# belamini_breakout_v01.net
KiCad netlist of a schematic drawn in EAGLE
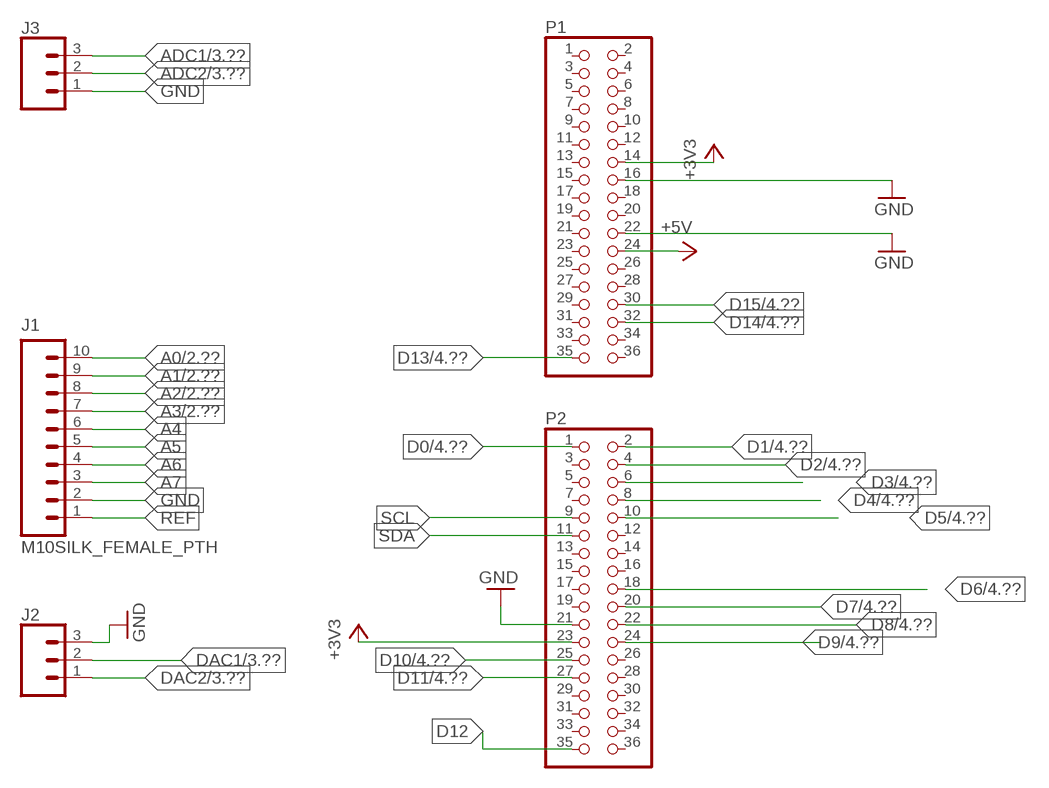
[diagram p0: schematic, sheet 1]
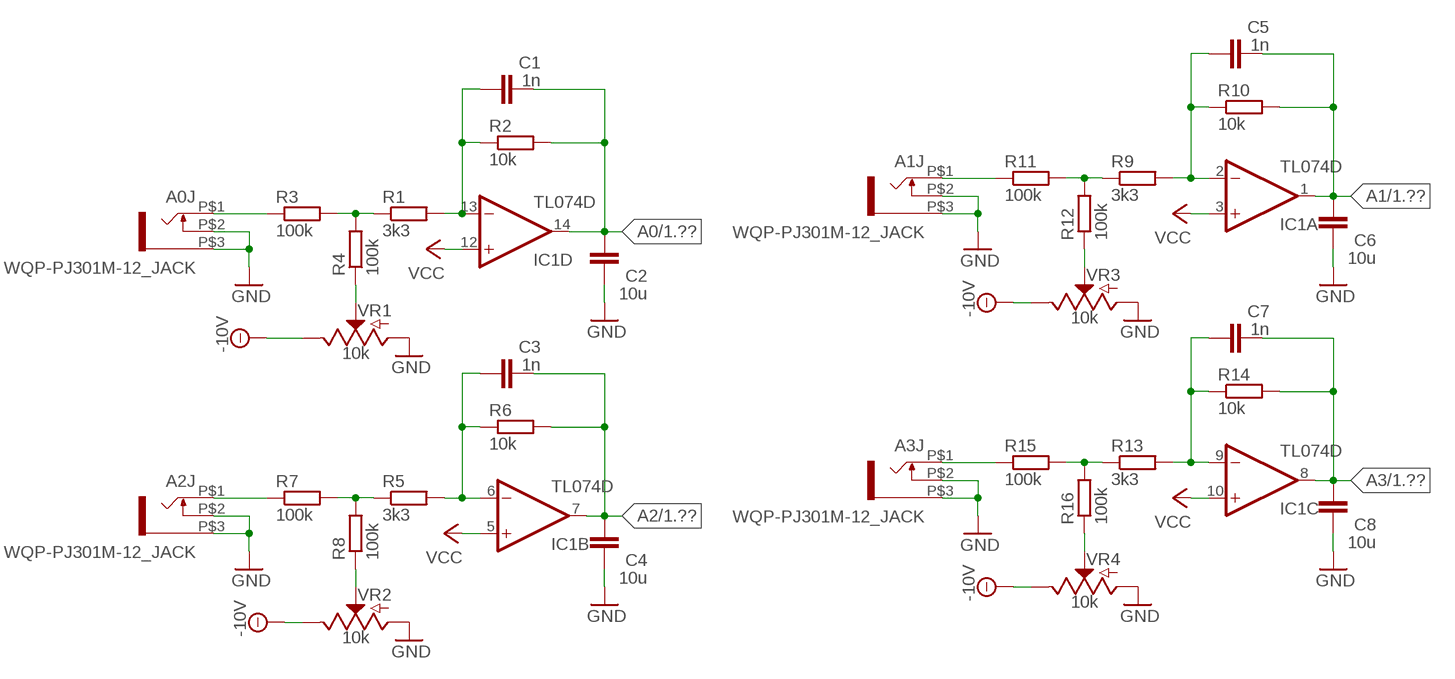
[diagram p1: schematic, sheet 2]
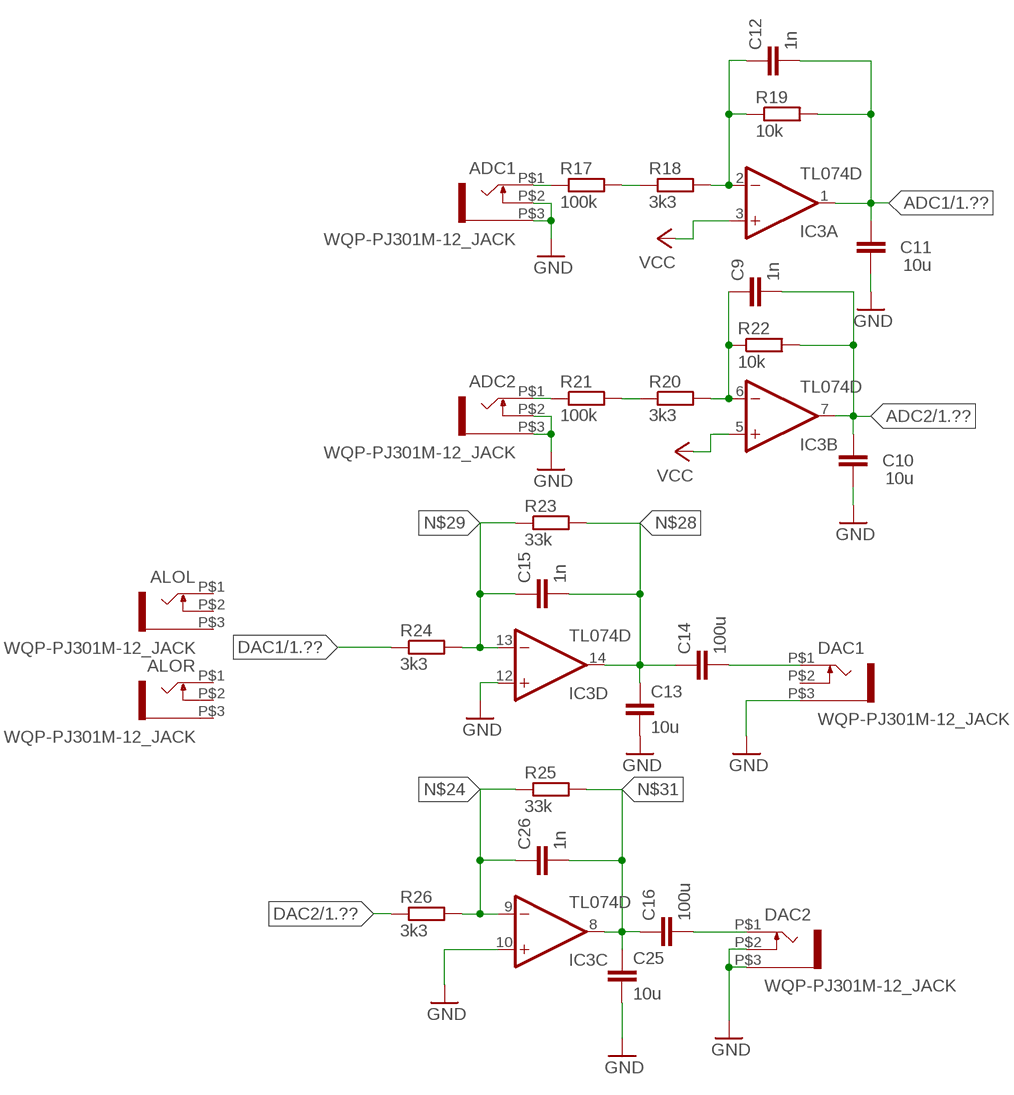
[diagram p2: schematic, sheet 3]
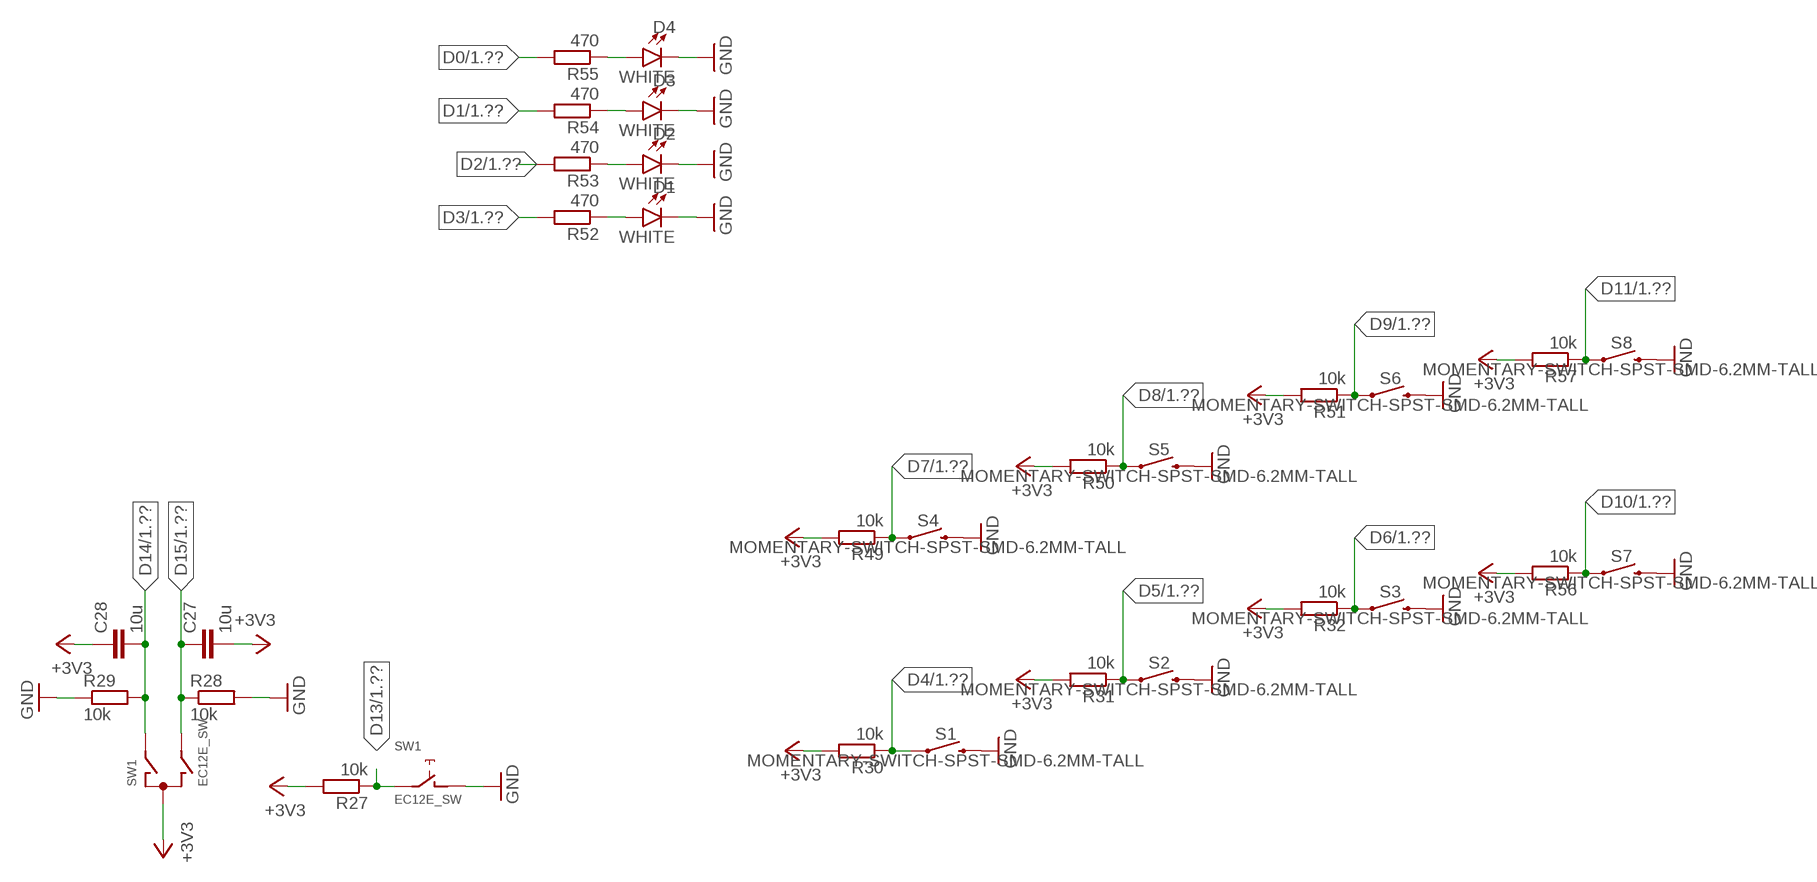
[diagram p3: schematic, sheet 4]
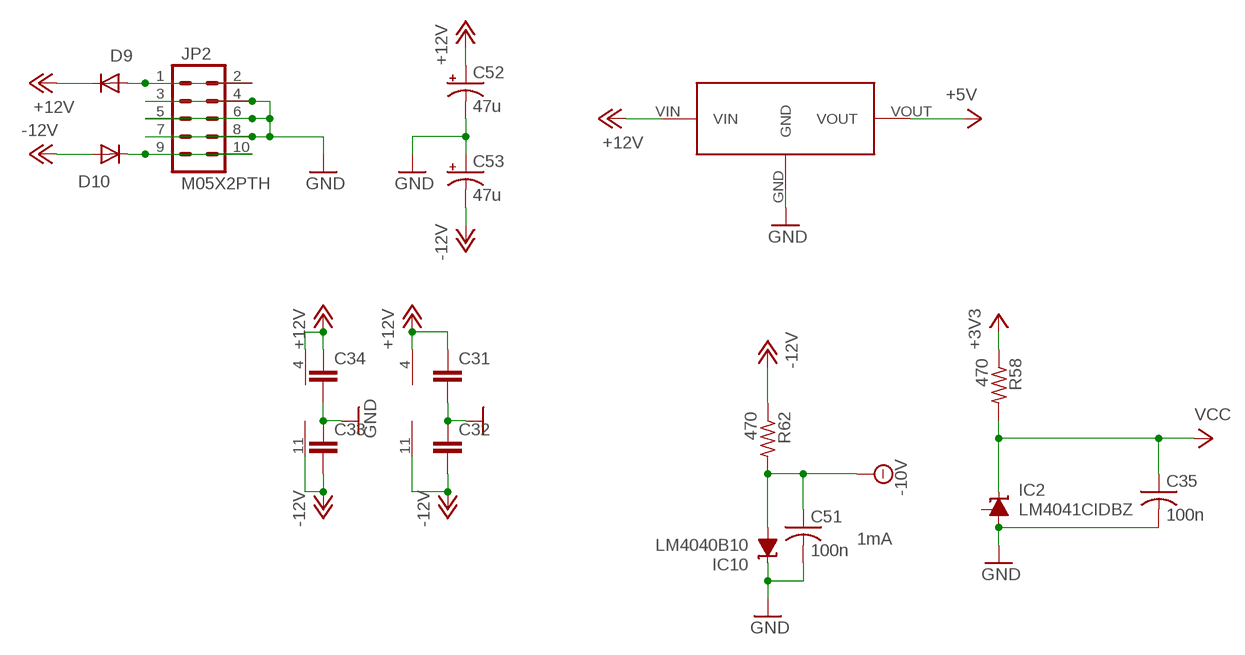
[diagram p4: schematic, sheet 5]

(export (version "E")
  (design (tool "Eeschema 10.0.6"))
  (components
    (comp (ref "C27")
      (value "10u")
      (footprint "eagle-import:C0603")
      (libsource (lib "eagle-import") (part "C-EUC0603"))
    )
    (comp (ref "C28")
      (value "10u")
      (footprint "eagle-import:C0603")
      (libsource (lib "eagle-import") (part "C-EUC0603"))
    )
    (comp (ref "D1")
      (value "WHITE")
      (footprint "eagle-import:LED-1206")
      (libsource (lib "eagle-import") (part "LED-WHITE1206"))
    )
    (comp (ref "D2")
      (value "WHITE")
      (footprint "eagle-import:LED-1206")
      (libsource (lib "eagle-import") (part "LED-WHITE1206"))
    )
    (comp (ref "D3")
      (value "WHITE")
      (footprint "eagle-import:LED-1206")
      (libsource (lib "eagle-import") (part "LED-WHITE1206"))
    )
    (comp (ref "D4")
      (value "WHITE")
      (footprint "eagle-import:LED-1206")
      (libsource (lib "eagle-import") (part "LED-WHITE1206"))
    )
    (comp (ref "R27")
      (value "10k")
      (footprint "eagle-import:R0603")
      (libsource (lib "eagle-import") (part "R-EU_R0603"))
    )
    (comp (ref "R28")
      (value "10k")
      (footprint "eagle-import:R0603")
      (libsource (lib "eagle-import") (part "R-EU_R0603"))
    )
    (comp (ref "R29")
      (value "10k")
      (footprint "eagle-import:R0603")
      (libsource (lib "eagle-import") (part "R-EU_R0603"))
    )
    (comp (ref "R30")
      (value "10k")
      (footprint "eagle-import:R0603")
      (libsource (lib "eagle-import") (part "R-EU_R0603"))
    )
    (comp (ref "R31")
      (value "10k")
      (footprint "eagle-import:R0603")
      (libsource (lib "eagle-import") (part "R-EU_R0603"))
    )
    (comp (ref "R32")
      (value "10k")
      (footprint "eagle-import:R0603")
      (libsource (lib "eagle-import") (part "R-EU_R0603"))
    )
    (comp (ref "R49")
      (value "10k")
      (footprint "eagle-import:R0603")
      (libsource (lib "eagle-import") (part "R-EU_R0603"))
    )
    (comp (ref "R50")
      (value "10k")
      (footprint "eagle-import:R0603")
      (libsource (lib "eagle-import") (part "R-EU_R0603"))
    )
    (comp (ref "R51")
      (value "10k")
      (footprint "eagle-import:R0603")
      (libsource (lib "eagle-import") (part "R-EU_R0603"))
    )
    (comp (ref "R52")
      (value "470")
      (footprint "eagle-import:R0603")
      (libsource (lib "eagle-import") (part "R-EU_R0603"))
    )
    (comp (ref "R53")
      (value "470")
      (footprint "eagle-import:R0603")
      (libsource (lib "eagle-import") (part "R-EU_R0603"))
    )
    (comp (ref "R54")
      (value "470")
      (footprint "eagle-import:R0603")
      (libsource (lib "eagle-import") (part "R-EU_R0603"))
    )
    (comp (ref "R55")
      (value "470")
      (footprint "eagle-import:R0603")
      (libsource (lib "eagle-import") (part "R-EU_R0603"))
    )
    (comp (ref "R56")
      (value "10k")
      (footprint "eagle-import:R0603")
      (libsource (lib "eagle-import") (part "R-EU_R0603"))
    )
    (comp (ref "R57")
      (value "10k")
      (footprint "eagle-import:R0603")
      (libsource (lib "eagle-import") (part "R-EU_R0603"))
    )
    (comp (ref "S1")
      (value "MOMENTARY-SWITCH-SPST-SMD-6.2MM-TALL")
      (footprint "eagle-import:TACTILE_SWITCH_SMD_6.2MM_TALL")
      (libsource (lib "eagle-import") (part "MOMENTARY-SWITCH-SPST-SMD-6.2MM-TALL"))
    )
    (comp (ref "S2")
      (value "MOMENTARY-SWITCH-SPST-SMD-6.2MM-TALL")
      (footprint "eagle-import:TACTILE_SWITCH_SMD_6.2MM_TALL")
      (libsource (lib "eagle-import") (part "MOMENTARY-SWITCH-SPST-SMD-6.2MM-TALL"))
    )
    (comp (ref "S3")
      (value "MOMENTARY-SWITCH-SPST-SMD-6.2MM-TALL")
      (footprint "eagle-import:TACTILE_SWITCH_SMD_6.2MM_TALL")
      (libsource (lib "eagle-import") (part "MOMENTARY-SWITCH-SPST-SMD-6.2MM-TALL"))
    )
    (comp (ref "S4")
      (value "MOMENTARY-SWITCH-SPST-SMD-6.2MM-TALL")
      (footprint "eagle-import:TACTILE_SWITCH_SMD_6.2MM_TALL")
      (libsource (lib "eagle-import") (part "MOMENTARY-SWITCH-SPST-SMD-6.2MM-TALL"))
    )
    (comp (ref "S5")
      (value "MOMENTARY-SWITCH-SPST-SMD-6.2MM-TALL")
      (footprint "eagle-import:TACTILE_SWITCH_SMD_6.2MM_TALL")
      (libsource (lib "eagle-import") (part "MOMENTARY-SWITCH-SPST-SMD-6.2MM-TALL"))
    )
    (comp (ref "S6")
      (value "MOMENTARY-SWITCH-SPST-SMD-6.2MM-TALL")
      (footprint "eagle-import:TACTILE_SWITCH_SMD_6.2MM_TALL")
      (libsource (lib "eagle-import") (part "MOMENTARY-SWITCH-SPST-SMD-6.2MM-TALL"))
    )
    (comp (ref "S7")
      (value "MOMENTARY-SWITCH-SPST-SMD-6.2MM-TALL")
      (footprint "eagle-import:TACTILE_SWITCH_SMD_6.2MM_TALL")
      (libsource (lib "eagle-import") (part "MOMENTARY-SWITCH-SPST-SMD-6.2MM-TALL"))
    )
    (comp (ref "S8")
      (value "MOMENTARY-SWITCH-SPST-SMD-6.2MM-TALL")
      (footprint "eagle-import:TACTILE_SWITCH_SMD_6.2MM_TALL")
      (libsource (lib "eagle-import") (part "MOMENTARY-SWITCH-SPST-SMD-6.2MM-TALL"))
    )
    (comp (ref "SW1")
      (value "EC12E_SW")
      (footprint "eagle-import:ALPS_EC12E_SW")
      (fields (field (name "MPN") "EC12E2424407"))
      (libsource (lib "eagle-import") (part "EC12E_SW"))
    )
    (comp (ref "J1")
      (value "M10SILK_FEMALE_PTH")
      (footprint "eagle-import:1X10")
      (libsource (lib "eagle-import") (part "M10SILK_FEMALE_PTH"))
    )
    (comp (ref "J2")
      (value "CONN_03")
      (footprint "eagle-import:1X03")
      (libsource (lib "eagle-import") (part "CONN_03"))
    )
    (comp (ref "J3")
      (value "CONN_03")
      (footprint "eagle-import:1X03")
      (libsource (lib "eagle-import") (part "CONN_03"))
    )
    (comp (ref "P1")
      (value "PINHD-2X18")
      (footprint "eagle-import:2X18")
      (libsource (lib "eagle-import") (part "PINHD-2X18"))
    )
    (comp (ref "P2")
      (value "PINHD-2X18")
      (footprint "eagle-import:2X18")
      (libsource (lib "eagle-import") (part "PINHD-2X18"))
    )
    (comp (ref "C31")
      (value "C-EUC0603")
      (footprint "eagle-import:C0603")
      (libsource (lib "eagle-import") (part "C-EUC0603"))
    )
    (comp (ref "C32")
      (value "C-EUC0603")
      (footprint "eagle-import:C0603")
      (libsource (lib "eagle-import") (part "C-EUC0603"))
    )
    (comp (ref "C33")
      (value "C-EUC0603")
      (footprint "eagle-import:C0603")
      (libsource (lib "eagle-import") (part "C-EUC0603"))
    )
    (comp (ref "C34")
      (value "C-EUC0603")
      (footprint "eagle-import:C0603")
      (libsource (lib "eagle-import") (part "C-EUC0603"))
    )
    (comp (ref "C35")
      (value "100n")
      (footprint "eagle-import:C0603")
      (libsource (lib "eagle-import") (part "C-USC0603"))
    )
    (comp (ref "C51")
      (value "100n")
      (footprint "eagle-import:C0603")
      (libsource (lib "eagle-import") (part "C-USC0603"))
    )
    (comp (ref "C52")
      (value "47u")
      (footprint "eagle-import:PANASONIC_D")
      (libsource (lib "eagle-import") (part "CPOL-USD"))
    )
    (comp (ref "C53")
      (value "47u")
      (footprint "eagle-import:PANASONIC_D")
      (libsource (lib "eagle-import") (part "CPOL-USD"))
    )
    (comp (ref "D9")
      (value "1N5819HW")
      (footprint "eagle-import:SOD123")
      (libsource (lib "eagle-import") (part "DIODE-SOD123"))
    )
    (comp (ref "D10")
      (value "1N5819HW")
      (footprint "eagle-import:SOD123")
      (libsource (lib "eagle-import") (part "DIODE-SOD123"))
    )
    (comp (ref "IC1")
      (value "TL074D")
      (footprint "eagle-import:SO14")
      (libsource (lib "eagle-import") (part "TL074D"))
    )
    (comp (ref "IC2")
      (value "LM4041CIDBZ")
      (footprint "eagle-import:DBZ_R-PDSO-G3")
      (fields (field (name "MF") "TEXAS INSTRUMENT CONNECTORS") (field (name "MPN") "LM4041CIDBZR"))
      (libsource (lib "eagle-import") (part "LM4041IDBZC"))
    )
    (comp (ref "IC3")
      (value "TL074D")
      (footprint "eagle-import:SO14")
      (libsource (lib "eagle-import") (part "TL074D"))
    )
    (comp (ref "IC10")
      (value "LM4040B10")
      (footprint "eagle-import:DBZ_R-PDSO-G3")
      (libsource (lib "eagle-import") (part "LM4041DBZB12"))
    )
    (comp (ref "JP2")
      (value "M05X2PTH")
      (footprint "eagle-import:AVR_ICSP")
      (libsource (lib "eagle-import") (part "M05X2PTH"))
    )
    (comp (ref "R58")
      (value "470")
      (footprint "eagle-import:R0603")
      (libsource (lib "eagle-import") (part "R-US_R0603"))
    )
    (comp (ref "R62")
      (value "470")
      (footprint "eagle-import:R0603")
      (libsource (lib "eagle-import") (part "R-US_R0603"))
    )
    (comp (ref "U$1")
      (value "RECOM785.0")
      (footprint "eagle-import:R-78XX-1.0")
      (libsource (lib "eagle-import") (part "RECOM785.0"))
    )
    (comp (ref "A0J")
      (value "WQP-PJ301M-12_JACK")
      (footprint "eagle-import:WQP-PJ301M-12_JACK")
      (libsource (lib "eagle-import") (part "WQP-PJ301M-12_JACK"))
    )
    (comp (ref "A1J")
      (value "WQP-PJ301M-12_JACK")
      (footprint "eagle-import:WQP-PJ301M-12_JACK")
      (libsource (lib "eagle-import") (part "WQP-PJ301M-12_JACK"))
    )
    (comp (ref "A2J")
      (value "WQP-PJ301M-12_JACK")
      (footprint "eagle-import:WQP-PJ301M-12_JACK")
      (libsource (lib "eagle-import") (part "WQP-PJ301M-12_JACK"))
    )
    (comp (ref "A3J")
      (value "WQP-PJ301M-12_JACK")
      (footprint "eagle-import:WQP-PJ301M-12_JACK")
      (libsource (lib "eagle-import") (part "WQP-PJ301M-12_JACK"))
    )
    (comp (ref "C1")
      (value "1n")
      (footprint "eagle-import:C0603")
      (libsource (lib "eagle-import") (part "C-EUC0603"))
    )
    (comp (ref "C2")
      (value "10u")
      (footprint "eagle-import:C0603")
      (libsource (lib "eagle-import") (part "C-EUC0603"))
    )
    (comp (ref "C3")
      (value "1n")
      (footprint "eagle-import:C0603")
      (libsource (lib "eagle-import") (part "C-EUC0603"))
    )
    (comp (ref "C4")
      (value "10u")
      (footprint "eagle-import:C0603")
      (libsource (lib "eagle-import") (part "C-EUC0603"))
    )
    (comp (ref "C5")
      (value "1n")
      (footprint "eagle-import:C0603")
      (libsource (lib "eagle-import") (part "C-EUC0603"))
    )
    (comp (ref "C6")
      (value "10u")
      (footprint "eagle-import:C0603")
      (libsource (lib "eagle-import") (part "C-EUC0603"))
    )
    (comp (ref "C7")
      (value "1n")
      (footprint "eagle-import:C0603")
      (libsource (lib "eagle-import") (part "C-EUC0603"))
    )
    (comp (ref "C8")
      (value "10u")
      (footprint "eagle-import:C0603")
      (libsource (lib "eagle-import") (part "C-EUC0603"))
    )
    (comp (ref "R1")
      (value "3k3")
      (footprint "eagle-import:R0603")
      (libsource (lib "eagle-import") (part "R-EU_R0603"))
    )
    (comp (ref "R2")
      (value "10k")
      (footprint "eagle-import:R0603")
      (libsource (lib "eagle-import") (part "R-EU_R0603"))
    )
    (comp (ref "R3")
      (value "100k")
      (footprint "eagle-import:R0603")
      (libsource (lib "eagle-import") (part "R-EU_R0603"))
    )
    (comp (ref "R4")
      (value "100k")
      (footprint "eagle-import:R0603")
      (libsource (lib "eagle-import") (part "R-EU_R0603"))
    )
    (comp (ref "R5")
      (value "3k3")
      (footprint "eagle-import:R0603")
      (libsource (lib "eagle-import") (part "R-EU_R0603"))
    )
    (comp (ref "R6")
      (value "10k")
      (footprint "eagle-import:R0603")
      (libsource (lib "eagle-import") (part "R-EU_R0603"))
    )
    (comp (ref "R7")
      (value "100k")
      (footprint "eagle-import:R0603")
      (libsource (lib "eagle-import") (part "R-EU_R0603"))
    )
    (comp (ref "R8")
      (value "100k")
      (footprint "eagle-import:R0603")
      (libsource (lib "eagle-import") (part "R-EU_R0603"))
    )
    (comp (ref "R9")
      (value "3k3")
      (footprint "eagle-import:R0603")
      (libsource (lib "eagle-import") (part "R-EU_R0603"))
    )
    (comp (ref "R10")
      (value "10k")
      (footprint "eagle-import:R0603")
      (libsource (lib "eagle-import") (part "R-EU_R0603"))
    )
    (comp (ref "R11")
      (value "100k")
      (footprint "eagle-import:R0603")
      (libsource (lib "eagle-import") (part "R-EU_R0603"))
    )
    (comp (ref "R12")
      (value "100k")
      (footprint "eagle-import:R0603")
      (libsource (lib "eagle-import") (part "R-EU_R0603"))
    )
    (comp (ref "R13")
      (value "3k3")
      (footprint "eagle-import:R0603")
      (libsource (lib "eagle-import") (part "R-EU_R0603"))
    )
    (comp (ref "R14")
      (value "10k")
      (footprint "eagle-import:R0603")
      (libsource (lib "eagle-import") (part "R-EU_R0603"))
    )
    (comp (ref "R15")
      (value "100k")
      (footprint "eagle-import:R0603")
      (libsource (lib "eagle-import") (part "R-EU_R0603"))
    )
    (comp (ref "R16")
      (value "100k")
      (footprint "eagle-import:R0603")
      (libsource (lib "eagle-import") (part "R-EU_R0603"))
    )
    (comp (ref "VR1")
      (value "10k")
      (footprint "eagle-import:POT-PTH-ALPS-KIT")
      (libsource (lib "eagle-import") (part "POTENTIOMETER-PTH-9MM-1/20W-20%-KIT"))
    )
    (comp (ref "VR2")
      (value "10k")
      (footprint "eagle-import:POT-PTH-ALPS-KIT")
      (libsource (lib "eagle-import") (part "POTENTIOMETER-PTH-9MM-1/20W-20%-KIT"))
    )
    (comp (ref "VR3")
      (value "10k")
      (footprint "eagle-import:POT-PTH-ALPS-KIT")
      (libsource (lib "eagle-import") (part "POTENTIOMETER-PTH-9MM-1/20W-20%-KIT"))
    )
    (comp (ref "VR4")
      (value "10k")
      (footprint "eagle-import:POT-PTH-ALPS-KIT")
      (libsource (lib "eagle-import") (part "POTENTIOMETER-PTH-9MM-1/20W-20%-KIT"))
    )
    (comp (ref "ADC1")
      (value "WQP-PJ301M-12_JACK")
      (footprint "eagle-import:WQP-PJ301M-12_JACK")
      (libsource (lib "eagle-import") (part "WQP-PJ301M-12_JACK"))
    )
    (comp (ref "ADC2")
      (value "WQP-PJ301M-12_JACK")
      (footprint "eagle-import:WQP-PJ301M-12_JACK")
      (libsource (lib "eagle-import") (part "WQP-PJ301M-12_JACK"))
    )
    (comp (ref "ALOL")
      (value "WQP-PJ301M-12_JACK")
      (footprint "eagle-import:WQP-PJ301M-12_JACK")
      (libsource (lib "eagle-import") (part "WQP-PJ301M-12_JACK"))
    )
    (comp (ref "ALOR")
      (value "WQP-PJ301M-12_JACK")
      (footprint "eagle-import:WQP-PJ301M-12_JACK")
      (libsource (lib "eagle-import") (part "WQP-PJ301M-12_JACK"))
    )
    (comp (ref "C9")
      (value "1n")
      (footprint "eagle-import:C0603")
      (libsource (lib "eagle-import") (part "C-EUC0603"))
    )
    (comp (ref "C10")
      (value "10u")
      (footprint "eagle-import:C0603")
      (libsource (lib "eagle-import") (part "C-EUC0603"))
    )
    (comp (ref "C11")
      (value "10u")
      (footprint "eagle-import:C0603")
      (libsource (lib "eagle-import") (part "C-EUC0603"))
    )
    (comp (ref "C12")
      (value "1n")
      (footprint "eagle-import:C0603")
      (libsource (lib "eagle-import") (part "C-EUC0603"))
    )
    (comp (ref "C13")
      (value "10u")
      (footprint "eagle-import:C0603")
      (libsource (lib "eagle-import") (part "C-EUC0603"))
    )
    (comp (ref "C14")
      (value "100u")
      (footprint "eagle-import:C0603")
      (libsource (lib "eagle-import") (part "C-EUC0603"))
    )
    (comp (ref "C15")
      (value "1n")
      (footprint "eagle-import:C0603")
      (libsource (lib "eagle-import") (part "C-EUC0603"))
    )
    (comp (ref "C16")
      (value "100u")
      (footprint "eagle-import:C0603")
      (libsource (lib "eagle-import") (part "C-EUC0603"))
    )
    (comp (ref "C25")
      (value "10u")
      (footprint "eagle-import:C0603")
      (libsource (lib "eagle-import") (part "C-EUC0603"))
    )
    (comp (ref "C26")
      (value "1n")
      (footprint "eagle-import:C0603")
      (libsource (lib "eagle-import") (part "C-EUC0603"))
    )
    (comp (ref "DAC1")
      (value "WQP-PJ301M-12_JACK")
      (footprint "eagle-import:WQP-PJ301M-12_JACK")
      (libsource (lib "eagle-import") (part "WQP-PJ301M-12_JACK"))
    )
    (comp (ref "DAC2")
      (value "WQP-PJ301M-12_JACK")
      (footprint "eagle-import:WQP-PJ301M-12_JACK")
      (libsource (lib "eagle-import") (part "WQP-PJ301M-12_JACK"))
    )
    (comp (ref "R17")
      (value "100k")
      (footprint "eagle-import:R0603")
      (libsource (lib "eagle-import") (part "R-EU_R0603"))
    )
    (comp (ref "R18")
      (value "3k3")
      (footprint "eagle-import:R0603")
      (libsource (lib "eagle-import") (part "R-EU_R0603"))
    )
    (comp (ref "R19")
      (value "10k")
      (footprint "eagle-import:R0603")
      (libsource (lib "eagle-import") (part "R-EU_R0603"))
    )
    (comp (ref "R20")
      (value "3k3")
      (footprint "eagle-import:R0603")
      (libsource (lib "eagle-import") (part "R-EU_R0603"))
    )
    (comp (ref "R21")
      (value "100k")
      (footprint "eagle-import:R0603")
      (libsource (lib "eagle-import") (part "R-EU_R0603"))
    )
    (comp (ref "R22")
      (value "10k")
      (footprint "eagle-import:R0603")
      (libsource (lib "eagle-import") (part "R-EU_R0603"))
    )
    (comp (ref "R23")
      (value "33k")
      (footprint "eagle-import:R0603")
      (libsource (lib "eagle-import") (part "R-EU_R0603"))
    )
    (comp (ref "R24")
      (value "3k3")
      (footprint "eagle-import:R0603")
      (libsource (lib "eagle-import") (part "R-EU_R0603"))
    )
    (comp (ref "R25")
      (value "33k")
      (footprint "eagle-import:R0603")
      (libsource (lib "eagle-import") (part "R-EU_R0603"))
    )
    (comp (ref "R26")
      (value "3k3")
      (footprint "eagle-import:R0603")
      (libsource (lib "eagle-import") (part "R-EU_R0603"))
    )
  )
  (nets
    (net (code "1") (name "+3V3") (class "Default")
      (node (ref "C27") (pin "2") (pinfunction "2_2") (pintype "passive"))
      (node (ref "C28") (pin "1") (pinfunction "1_1") (pintype "passive"))
      (node (ref "P1") (pin "14") (pinfunction "14_14") (pintype "passive"))
      (node (ref "P2") (pin "23") (pinfunction "23_23") (pintype "passive"))
      (node (ref "R27") (pin "2") (pinfunction "2_2") (pintype "passive"))
      (node (ref "R30") (pin "2") (pinfunction "2_2") (pintype "passive"))
      (node (ref "R31") (pin "2") (pinfunction "2_2") (pintype "passive"))
      (node (ref "R32") (pin "2") (pinfunction "2_2") (pintype "passive"))
      (node (ref "R49") (pin "2") (pinfunction "2_2") (pintype "passive"))
      (node (ref "R50") (pin "2") (pinfunction "2_2") (pintype "passive"))
      (node (ref "R51") (pin "2") (pinfunction "2_2") (pintype "passive"))
      (node (ref "R56") (pin "2") (pinfunction "2_2") (pintype "passive"))
      (node (ref "R57") (pin "2") (pinfunction "2_2") (pintype "passive"))
      (node (ref "R58") (pin "1") (pinfunction "1_1") (pintype "passive"))
      (node (ref "SW1") (pin "C") (pinfunction "C_C") (pintype "passive"))
    )
    (net (code "2") (name "+5V") (class "Default")
      (node (ref "P1") (pin "24") (pinfunction "24_24") (pintype "passive"))
      (node (ref "U$1") (pin "VOUT") (pinfunction "VOUT_VOUT") (pintype "bidirectional"))
    )
    (net (code "3") (name "+12V") (class "Default")
      (node (ref "C31") (pin "1") (pinfunction "1_1") (pintype "passive"))
      (node (ref "C34") (pin "1") (pinfunction "1_1") (pintype "passive"))
      (node (ref "C52") (pin "+") (pinfunction "+_+") (pintype "passive"))
      (node (ref "D9") (pin "C") (pinfunction "C_C") (pintype "passive"))
      (node (ref "IC1") (pin "4") (pinfunction "V+_4") (pintype "power_in"))
      (node (ref "IC3") (pin "4") (pinfunction "V+_4") (pintype "power_in"))
      (node (ref "U$1") (pin "VIN") (pinfunction "VIN_VIN") (pintype "bidirectional"))
    )
    (net (code "4") (name "-10V") (class "Default")
      (node (ref "C51") (pin "1") (pinfunction "1_1") (pintype "passive"))
      (node (ref "IC10") (pin "2") (pinfunction "A_2") (pintype "passive"))
      (node (ref "R62") (pin "2") (pinfunction "2_2") (pintype "passive"))
      (node (ref "VR1") (pin "P$1") (pinfunction "E_P$1") (pintype "passive"))
      (node (ref "VR2") (pin "P$1") (pinfunction "E_P$1") (pintype "passive"))
      (node (ref "VR3") (pin "P$1") (pinfunction "E_P$1") (pintype "passive"))
      (node (ref "VR4") (pin "P$1") (pinfunction "E_P$1") (pintype "passive"))
    )
    (net (code "5") (name "-12V") (class "Default")
      (node (ref "C32") (pin "2") (pinfunction "2_2") (pintype "passive"))
      (node (ref "C33") (pin "2") (pinfunction "2_2") (pintype "passive"))
      (node (ref "C53") (pin "-") (pinfunction "-_-") (pintype "passive"))
      (node (ref "D10") (pin "A") (pinfunction "A_A") (pintype "passive"))
      (node (ref "IC1") (pin "11") (pinfunction "V-_11") (pintype "power_in"))
      (node (ref "IC3") (pin "11") (pinfunction "V-_11") (pintype "power_in"))
      (node (ref "R62") (pin "1") (pinfunction "1_1") (pintype "passive"))
    )
    (net (code "6") (name "A0") (class "Default")
      (node (ref "C1") (pin "2") (pinfunction "2_2") (pintype "passive"))
      (node (ref "C2") (pin "2") (pinfunction "2_2") (pintype "passive"))
      (node (ref "IC1") (pin "14") (pinfunction "OUT_14") (pintype "output"))
      (node (ref "J1") (pin "10") (pinfunction "10_10") (pintype "passive"))
      (node (ref "R2") (pin "2") (pinfunction "2_2") (pintype "passive"))
    )
    (net (code "7") (name "A1") (class "Default")
      (node (ref "C5") (pin "2") (pinfunction "2_2") (pintype "passive"))
      (node (ref "C6") (pin "2") (pinfunction "2_2") (pintype "passive"))
      (node (ref "IC1") (pin "1") (pinfunction "OUT_1") (pintype "output"))
      (node (ref "J1") (pin "9") (pinfunction "9_9") (pintype "passive"))
      (node (ref "R10") (pin "2") (pinfunction "2_2") (pintype "passive"))
    )
    (net (code "8") (name "A2") (class "Default")
      (node (ref "C3") (pin "2") (pinfunction "2_2") (pintype "passive"))
      (node (ref "C4") (pin "2") (pinfunction "2_2") (pintype "passive"))
      (node (ref "IC1") (pin "7") (pinfunction "OUT_7") (pintype "output"))
      (node (ref "J1") (pin "8") (pinfunction "8_8") (pintype "passive"))
      (node (ref "R6") (pin "2") (pinfunction "2_2") (pintype "passive"))
    )
    (net (code "9") (name "A3") (class "Default")
      (node (ref "C7") (pin "2") (pinfunction "2_2") (pintype "passive"))
      (node (ref "C8") (pin "2") (pinfunction "2_2") (pintype "passive"))
      (node (ref "IC1") (pin "8") (pinfunction "OUT_8") (pintype "output"))
      (node (ref "J1") (pin "7") (pinfunction "7_7") (pintype "passive"))
      (node (ref "R14") (pin "2") (pinfunction "2_2") (pintype "passive"))
    )
    (net (code "10") (name "A4") (class "Default")
      (node (ref "J1") (pin "6") (pinfunction "6_6") (pintype "passive"))
    )
    (net (code "11") (name "A5") (class "Default")
      (node (ref "J1") (pin "5") (pinfunction "5_5") (pintype "passive"))
    )
    (net (code "12") (name "A6") (class "Default")
      (node (ref "J1") (pin "4") (pinfunction "4_4") (pintype "passive"))
    )
    (net (code "13") (name "A7") (class "Default")
      (node (ref "J1") (pin "3") (pinfunction "3_3") (pintype "passive"))
    )
    (net (code "14") (name "ADC1") (class "Default")
      (node (ref "C11") (pin "2") (pinfunction "2_2") (pintype "passive"))
      (node (ref "C12") (pin "2") (pinfunction "2_2") (pintype "passive"))
      (node (ref "IC3") (pin "1") (pinfunction "OUT_1") (pintype "output"))
      (node (ref "J3") (pin "3") (pinfunction "3_3") (pintype "passive"))
      (node (ref "R19") (pin "2") (pinfunction "2_2") (pintype "passive"))
    )
    (net (code "15") (name "ADC2") (class "Default")
      (node (ref "C10") (pin "2") (pinfunction "2_2") (pintype "passive"))
      (node (ref "C9") (pin "2") (pinfunction "2_2") (pintype "passive"))
      (node (ref "IC3") (pin "7") (pinfunction "OUT_7") (pintype "output"))
      (node (ref "J3") (pin "2") (pinfunction "2_2") (pintype "passive"))
      (node (ref "R22") (pin "2") (pinfunction "2_2") (pintype "passive"))
    )
    (net (code "16") (name "D0") (class "Default")
      (node (ref "P2") (pin "1") (pinfunction "1_1") (pintype "passive"))
      (node (ref "R55") (pin "2") (pinfunction "2_2") (pintype "passive"))
    )
    (net (code "17") (name "D1") (class "Default")
      (node (ref "P2") (pin "2") (pinfunction "2_2") (pintype "passive"))
      (node (ref "R54") (pin "2") (pinfunction "2_2") (pintype "passive"))
    )
    (net (code "18") (name "D2") (class "Default")
      (node (ref "P2") (pin "4") (pinfunction "4_4") (pintype "passive"))
      (node (ref "R53") (pin "2") (pinfunction "2_2") (pintype "passive"))
    )
    (net (code "19") (name "D3") (class "Default")
      (node (ref "P2") (pin "6") (pinfunction "6_6") (pintype "passive"))
      (node (ref "R52") (pin "2") (pinfunction "2_2") (pintype "passive"))
    )
    (net (code "20") (name "D4") (class "Default")
      (node (ref "P2") (pin "8") (pinfunction "8_8") (pintype "passive"))
      (node (ref "R30") (pin "1") (pinfunction "1_1") (pintype "passive"))
      (node (ref "S1") (pin "A2") (pinfunction "1_A2") (pintype "passive"))
    )
    (net (code "21") (name "D5") (class "Default")
      (node (ref "P2") (pin "10") (pinfunction "10_10") (pintype "passive"))
      (node (ref "R31") (pin "1") (pinfunction "1_1") (pintype "passive"))
      (node (ref "S2") (pin "A2") (pinfunction "1_A2") (pintype "passive"))
    )
    (net (code "22") (name "D6") (class "Default")
      (node (ref "P2") (pin "18") (pinfunction "18_18") (pintype "passive"))
      (node (ref "R32") (pin "1") (pinfunction "1_1") (pintype "passive"))
      (node (ref "S3") (pin "A2") (pinfunction "1_A2") (pintype "passive"))
    )
    (net (code "23") (name "D7") (class "Default")
      (node (ref "P2") (pin "20") (pinfunction "20_20") (pintype "passive"))
      (node (ref "R49") (pin "1") (pinfunction "1_1") (pintype "passive"))
      (node (ref "S4") (pin "A2") (pinfunction "1_A2") (pintype "passive"))
    )
    (net (code "24") (name "D8") (class "Default")
      (node (ref "P2") (pin "22") (pinfunction "22_22") (pintype "passive"))
      (node (ref "R50") (pin "1") (pinfunction "1_1") (pintype "passive"))
      (node (ref "S5") (pin "A2") (pinfunction "1_A2") (pintype "passive"))
    )
    (net (code "25") (name "D9") (class "Default")
      (node (ref "P2") (pin "24") (pinfunction "24_24") (pintype "passive"))
      (node (ref "R51") (pin "1") (pinfunction "1_1") (pintype "passive"))
      (node (ref "S6") (pin "A2") (pinfunction "1_A2") (pintype "passive"))
    )
    (net (code "26") (name "D10") (class "Default")
      (node (ref "P2") (pin "25") (pinfunction "25_25") (pintype "passive"))
      (node (ref "R56") (pin "1") (pinfunction "1_1") (pintype "passive"))
      (node (ref "S7") (pin "A2") (pinfunction "1_A2") (pintype "passive"))
    )
    (net (code "27") (name "D11") (class "Default")
      (node (ref "P2") (pin "27") (pinfunction "27_27") (pintype "passive"))
      (node (ref "R57") (pin "1") (pinfunction "1_1") (pintype "passive"))
      (node (ref "S8") (pin "A2") (pinfunction "1_A2") (pintype "passive"))
    )
    (net (code "28") (name "D12") (class "Default")
      (node (ref "P2") (pin "35") (pinfunction "35_35") (pintype "passive"))
    )
    (net (code "29") (name "D13") (class "Default")
      (node (ref "P1") (pin "35") (pinfunction "35_35") (pintype "passive"))
      (node (ref "R27") (pin "1") (pinfunction "1_1") (pintype "passive"))
      (node (ref "SW1") (pin "E") (pinfunction "2_E") (pintype "passive"))
    )
    (net (code "30") (name "D14") (class "Default")
      (node (ref "C28") (pin "2") (pinfunction "2_2") (pintype "passive"))
      (node (ref "P1") (pin "32") (pinfunction "32_32") (pintype "passive"))
      (node (ref "R29") (pin "2") (pinfunction "2_2") (pintype "passive"))
      (node (ref "SW1") (pin "A") (pinfunction "A_A") (pintype "passive"))
    )
    (net (code "31") (name "D15") (class "Default")
      (node (ref "C27") (pin "1") (pinfunction "1_1") (pintype "passive"))
      (node (ref "P1") (pin "30") (pinfunction "30_30") (pintype "passive"))
      (node (ref "R28") (pin "1") (pinfunction "1_1") (pintype "passive"))
      (node (ref "SW1") (pin "B") (pinfunction "B_B") (pintype "passive"))
    )
    (net (code "32") (name "DAC1") (class "Default")
      (node (ref "J2") (pin "2") (pinfunction "2_2") (pintype "passive"))
      (node (ref "R24") (pin "1") (pinfunction "1_1") (pintype "passive"))
    )
    (net (code "33") (name "DAC2") (class "Default")
      (node (ref "J2") (pin "1") (pinfunction "1_1") (pintype "passive"))
      (node (ref "R26") (pin "1") (pinfunction "1_1") (pintype "passive"))
    )
    (net (code "34") (name "GND") (class "Default")
      (node (ref "A0J") (pin "P$2") (pinfunction "3_P$2") (pintype "passive"))
      (node (ref "A0J") (pin "P$3") (pinfunction "1_P$3") (pintype "passive"))
      (node (ref "A1J") (pin "P$2") (pinfunction "3_P$2") (pintype "passive"))
      (node (ref "A1J") (pin "P$3") (pinfunction "1_P$3") (pintype "passive"))
      (node (ref "A2J") (pin "P$2") (pinfunction "3_P$2") (pintype "passive"))
      (node (ref "A2J") (pin "P$3") (pinfunction "1_P$3") (pintype "passive"))
      (node (ref "A3J") (pin "P$2") (pinfunction "3_P$2") (pintype "passive"))
      (node (ref "A3J") (pin "P$3") (pinfunction "1_P$3") (pintype "passive"))
      (node (ref "ADC1") (pin "P$2") (pinfunction "3_P$2") (pintype "passive"))
      (node (ref "ADC1") (pin "P$3") (pinfunction "1_P$3") (pintype "passive"))
      (node (ref "ADC2") (pin "P$2") (pinfunction "3_P$2") (pintype "passive"))
      (node (ref "ADC2") (pin "P$3") (pinfunction "1_P$3") (pintype "passive"))
      (node (ref "C10") (pin "1") (pinfunction "1_1") (pintype "passive"))
      (node (ref "C11") (pin "1") (pinfunction "1_1") (pintype "passive"))
      (node (ref "C13") (pin "2") (pinfunction "2_2") (pintype "passive"))
      (node (ref "C2") (pin "1") (pinfunction "1_1") (pintype "passive"))
      (node (ref "C25") (pin "2") (pinfunction "2_2") (pintype "passive"))
      (node (ref "C31") (pin "2") (pinfunction "2_2") (pintype "passive"))
      (node (ref "C32") (pin "1") (pinfunction "1_1") (pintype "passive"))
      (node (ref "C33") (pin "1") (pinfunction "1_1") (pintype "passive"))
      (node (ref "C34") (pin "2") (pinfunction "2_2") (pintype "passive"))
      (node (ref "C35") (pin "2") (pinfunction "2_2") (pintype "passive"))
      (node (ref "C4") (pin "1") (pinfunction "1_1") (pintype "passive"))
      (node (ref "C51") (pin "2") (pinfunction "2_2") (pintype "passive"))
      (node (ref "C52") (pin "-") (pinfunction "-_-") (pintype "passive"))
      (node (ref "C53") (pin "+") (pinfunction "+_+") (pintype "passive"))
      (node (ref "C6") (pin "1") (pinfunction "1_1") (pintype "passive"))
      (node (ref "C8") (pin "1") (pinfunction "1_1") (pintype "passive"))
      (node (ref "D1") (pin "C") (pinfunction "C_C") (pintype "passive"))
      (node (ref "D2") (pin "C") (pinfunction "C_C") (pintype "passive"))
      (node (ref "D3") (pin "C") (pinfunction "C_C") (pintype "passive"))
      (node (ref "D4") (pin "C") (pinfunction "C_C") (pintype "passive"))
      (node (ref "DAC1") (pin "P$3") (pinfunction "1_P$3") (pintype "passive"))
      (node (ref "DAC2") (pin "P$2") (pinfunction "3_P$2") (pintype "passive"))
      (node (ref "DAC2") (pin "P$3") (pinfunction "1_P$3") (pintype "passive"))
      (node (ref "IC10") (pin "1") (pinfunction "C_1") (pintype "passive"))
      (node (ref "IC2") (pin "3") (pinfunction "A_3") (pintype "passive"))
      (node (ref "IC3") (pin "10") (pinfunction "+IN_10") (pintype "input"))
      (node (ref "IC3") (pin "12") (pinfunction "+IN_12") (pintype "input"))
      (node (ref "J1") (pin "2") (pinfunction "2_2") (pintype "passive"))
      (node (ref "J2") (pin "3") (pinfunction "3_3") (pintype "passive"))
      (node (ref "J3") (pin "1") (pinfunction "1_1") (pintype "passive"))
      (node (ref "JP2") (pin "3") (pinfunction "3_3") (pintype "passive"))
      (node (ref "JP2") (pin "4") (pinfunction "4_4") (pintype "passive"))
      (node (ref "JP2") (pin "5") (pinfunction "5_5") (pintype "passive"))
      (node (ref "JP2") (pin "6") (pinfunction "6_6") (pintype "passive"))
      (node (ref "JP2") (pin "7") (pinfunction "7_7") (pintype "passive"))
      (node (ref "JP2") (pin "8") (pinfunction "8_8") (pintype "passive"))
      (node (ref "P1") (pin "16") (pinfunction "16_16") (pintype "passive"))
      (node (ref "P1") (pin "22") (pinfunction "22_22") (pintype "passive"))
      (node (ref "P2") (pin "21") (pinfunction "21_21") (pintype "passive"))
      (node (ref "R28") (pin "2") (pinfunction "2_2") (pintype "passive"))
      (node (ref "R29") (pin "1") (pinfunction "1_1") (pintype "passive"))
      (node (ref "S1") (pin "B2") (pinfunction "2_B2") (pintype "passive"))
      (node (ref "S2") (pin "B2") (pinfunction "2_B2") (pintype "passive"))
      (node (ref "S3") (pin "B2") (pinfunction "2_B2") (pintype "passive"))
      (node (ref "S4") (pin "B2") (pinfunction "2_B2") (pintype "passive"))
      (node (ref "S5") (pin "B2") (pinfunction "2_B2") (pintype "passive"))
      (node (ref "S6") (pin "B2") (pinfunction "2_B2") (pintype "passive"))
      (node (ref "S7") (pin "B2") (pinfunction "2_B2") (pintype "passive"))
      (node (ref "S8") (pin "B2") (pinfunction "2_B2") (pintype "passive"))
      (node (ref "SW1") (pin "D") (pinfunction "1_D") (pintype "passive"))
      (node (ref "U$1") (pin "GND") (pinfunction "GND_GND") (pintype "bidirectional"))
      (node (ref "VR1") (pin "P$3") (pinfunction "A_P$3") (pintype "passive"))
      (node (ref "VR2") (pin "P$3") (pinfunction "A_P$3") (pintype "passive"))
      (node (ref "VR3") (pin "P$3") (pinfunction "A_P$3") (pintype "passive"))
      (node (ref "VR4") (pin "P$3") (pinfunction "A_P$3") (pintype "passive"))
    )
    (net (code "35") (name "N$24") (class "Default")
      (node (ref "C26") (pin "1") (pinfunction "1_1") (pintype "passive"))
      (node (ref "IC3") (pin "9") (pinfunction "-IN_9") (pintype "input"))
      (node (ref "R25") (pin "1") (pinfunction "1_1") (pintype "passive"))
      (node (ref "R26") (pin "2") (pinfunction "2_2") (pintype "passive"))
    )
    (net (code "36") (name "N$28") (class "Default")
      (node (ref "C13") (pin "1") (pinfunction "1_1") (pintype "passive"))
      (node (ref "C14") (pin "1") (pinfunction "1_1") (pintype "passive"))
      (node (ref "C15") (pin "2") (pinfunction "2_2") (pintype "passive"))
      (node (ref "IC3") (pin "14") (pinfunction "OUT_14") (pintype "output"))
      (node (ref "R23") (pin "2") (pinfunction "2_2") (pintype "passive"))
    )
    (net (code "37") (name "N$29") (class "Default")
      (node (ref "C15") (pin "1") (pinfunction "1_1") (pintype "passive"))
      (node (ref "IC3") (pin "13") (pinfunction "-IN_13") (pintype "input"))
      (node (ref "R23") (pin "1") (pinfunction "1_1") (pintype "passive"))
      (node (ref "R24") (pin "2") (pinfunction "2_2") (pintype "passive"))
    )
    (net (code "38") (name "N$31") (class "Default")
      (node (ref "C16") (pin "1") (pinfunction "1_1") (pintype "passive"))
      (node (ref "C25") (pin "1") (pinfunction "1_1") (pintype "passive"))
      (node (ref "C26") (pin "2") (pinfunction "2_2") (pintype "passive"))
      (node (ref "IC3") (pin "8") (pinfunction "OUT_8") (pintype "output"))
      (node (ref "R25") (pin "2") (pinfunction "2_2") (pintype "passive"))
    )
    (net (code "39") (name "Net-(A0J-2)") (class "Default")
      (node (ref "A0J") (pin "P$1") (pinfunction "2_P$1") (pintype "passive"))
      (node (ref "R3") (pin "1") (pinfunction "1_1") (pintype "passive"))
    )
    (net (code "40") (name "Net-(A1J-2)") (class "Default")
      (node (ref "A1J") (pin "P$1") (pinfunction "2_P$1") (pintype "passive"))
      (node (ref "R11") (pin "1") (pinfunction "1_1") (pintype "passive"))
    )
    (net (code "41") (name "Net-(A2J-2)") (class "Default")
      (node (ref "A2J") (pin "P$1") (pinfunction "2_P$1") (pintype "passive"))
      (node (ref "R7") (pin "1") (pinfunction "1_1") (pintype "passive"))
    )
    (net (code "42") (name "Net-(A3J-2)") (class "Default")
      (node (ref "A3J") (pin "P$1") (pinfunction "2_P$1") (pintype "passive"))
      (node (ref "R15") (pin "1") (pinfunction "1_1") (pintype "passive"))
    )
    (net (code "43") (name "Net-(ADC1-2)") (class "Default")
      (node (ref "ADC1") (pin "P$1") (pinfunction "2_P$1") (pintype "passive"))
      (node (ref "R17") (pin "1") (pinfunction "1_1") (pintype "passive"))
    )
    (net (code "44") (name "Net-(ADC2-2)") (class "Default")
      (node (ref "ADC2") (pin "P$1") (pinfunction "2_P$1") (pintype "passive"))
      (node (ref "R21") (pin "1") (pinfunction "1_1") (pintype "passive"))
    )
    (net (code "45") (name "Net-(D1-PadA)") (class "Default")
      (node (ref "D1") (pin "A") (pinfunction "A_A") (pintype "passive"))
      (node (ref "R52") (pin "1") (pinfunction "1_1") (pintype "passive"))
    )
    (net (code "46") (name "Net-(D2-PadA)") (class "Default")
      (node (ref "D2") (pin "A") (pinfunction "A_A") (pintype "passive"))
      (node (ref "R53") (pin "1") (pinfunction "1_1") (pintype "passive"))
    )
    (net (code "47") (name "Net-(D3-PadA)") (class "Default")
      (node (ref "D3") (pin "A") (pinfunction "A_A") (pintype "passive"))
      (node (ref "R54") (pin "1") (pinfunction "1_1") (pintype "passive"))
    )
    (net (code "48") (name "Net-(D4-PadA)") (class "Default")
      (node (ref "D4") (pin "A") (pinfunction "A_A") (pintype "passive"))
      (node (ref "R55") (pin "1") (pinfunction "1_1") (pintype "passive"))
    )
    (net (code "49") (name "Net-(D9-PadA)") (class "Default")
      (node (ref "D9") (pin "A") (pinfunction "A_A") (pintype "passive"))
      (node (ref "JP2") (pin "1") (pinfunction "1_1") (pintype "passive"))
      (node (ref "JP2") (pin "2") (pinfunction "2_2") (pintype "passive"))
    )
    (net (code "50") (name "Net-(D10-PadC)") (class "Default")
      (node (ref "D10") (pin "C") (pinfunction "C_C") (pintype "passive"))
      (node (ref "JP2") (pin "10") (pinfunction "10_10") (pintype "passive"))
      (node (ref "JP2") (pin "9") (pinfunction "9_9") (pintype "passive"))
    )
    (net (code "51") (name "Net-(DAC1-2)") (class "Default")
      (node (ref "C14") (pin "2") (pinfunction "2_2") (pintype "passive"))
      (node (ref "DAC1") (pin "P$1") (pinfunction "2_P$1") (pintype "passive"))
    )
    (net (code "52") (name "Net-(DAC2-2)") (class "Default")
      (node (ref "C16") (pin "2") (pinfunction "2_2") (pintype "passive"))
      (node (ref "DAC2") (pin "P$1") (pinfunction "2_P$1") (pintype "passive"))
    )
    (net (code "53") (name "Net-(IC1A--IN)") (class "Default")
      (node (ref "C5") (pin "1") (pinfunction "1_1") (pintype "passive"))
      (node (ref "IC1") (pin "2") (pinfunction "-IN_2") (pintype "input"))
      (node (ref "R10") (pin "1") (pinfunction "1_1") (pintype "passive"))
      (node (ref "R9") (pin "2") (pinfunction "2_2") (pintype "passive"))
    )
    (net (code "54") (name "Net-(IC1B--IN)") (class "Default")
      (node (ref "C3") (pin "1") (pinfunction "1_1") (pintype "passive"))
      (node (ref "IC1") (pin "6") (pinfunction "-IN_6") (pintype "input"))
      (node (ref "R5") (pin "2") (pinfunction "2_2") (pintype "passive"))
      (node (ref "R6") (pin "1") (pinfunction "1_1") (pintype "passive"))
    )
    (net (code "55") (name "Net-(IC1C--IN)") (class "Default")
      (node (ref "C7") (pin "1") (pinfunction "1_1") (pintype "passive"))
      (node (ref "IC1") (pin "9") (pinfunction "-IN_9") (pintype "input"))
      (node (ref "R13") (pin "2") (pinfunction "2_2") (pintype "passive"))
      (node (ref "R14") (pin "1") (pinfunction "1_1") (pintype "passive"))
    )
    (net (code "56") (name "Net-(IC1D--IN)") (class "Default")
      (node (ref "C1") (pin "1") (pinfunction "1_1") (pintype "passive"))
      (node (ref "IC1") (pin "13") (pinfunction "-IN_13") (pintype "input"))
      (node (ref "R1") (pin "2") (pinfunction "2_2") (pintype "passive"))
      (node (ref "R2") (pin "1") (pinfunction "1_1") (pintype "passive"))
    )
    (net (code "57") (name "Net-(IC3A--IN)") (class "Default")
      (node (ref "C12") (pin "1") (pinfunction "1_1") (pintype "passive"))
      (node (ref "IC3") (pin "2") (pinfunction "-IN_2") (pintype "input"))
      (node (ref "R18") (pin "2") (pinfunction "2_2") (pintype "passive"))
      (node (ref "R19") (pin "1") (pinfunction "1_1") (pintype "passive"))
    )
    (net (code "58") (name "Net-(IC3B--IN)") (class "Default")
      (node (ref "C9") (pin "1") (pinfunction "1_1") (pintype "passive"))
      (node (ref "IC3") (pin "6") (pinfunction "-IN_6") (pintype "input"))
      (node (ref "R20") (pin "2") (pinfunction "2_2") (pintype "passive"))
      (node (ref "R22") (pin "1") (pinfunction "1_1") (pintype "passive"))
    )
    (net (code "59") (name "Net-(R1-Pad1)") (class "Default")
      (node (ref "R1") (pin "1") (pinfunction "1_1") (pintype "passive"))
      (node (ref "R3") (pin "2") (pinfunction "2_2") (pintype "passive"))
      (node (ref "R4") (pin "2") (pinfunction "2_2") (pintype "passive"))
    )
    (net (code "60") (name "Net-(R5-Pad1)") (class "Default")
      (node (ref "R5") (pin "1") (pinfunction "1_1") (pintype "passive"))
      (node (ref "R7") (pin "2") (pinfunction "2_2") (pintype "passive"))
      (node (ref "R8") (pin "2") (pinfunction "2_2") (pintype "passive"))
    )
    (net (code "61") (name "Net-(R11-Pad2)") (class "Default")
      (node (ref "R11") (pin "2") (pinfunction "2_2") (pintype "passive"))
      (node (ref "R12") (pin "2") (pinfunction "2_2") (pintype "passive"))
      (node (ref "R9") (pin "1") (pinfunction "1_1") (pintype "passive"))
    )
    (net (code "62") (name "Net-(R13-Pad1)") (class "Default")
      (node (ref "R13") (pin "1") (pinfunction "1_1") (pintype "passive"))
      (node (ref "R15") (pin "2") (pinfunction "2_2") (pintype "passive"))
      (node (ref "R16") (pin "2") (pinfunction "2_2") (pintype "passive"))
    )
    (net (code "63") (name "Net-(R17-Pad2)") (class "Default")
      (node (ref "R17") (pin "2") (pinfunction "2_2") (pintype "passive"))
      (node (ref "R18") (pin "1") (pinfunction "1_1") (pintype "passive"))
    )
    (net (code "64") (name "Net-(R20-Pad1)") (class "Default")
      (node (ref "R20") (pin "1") (pinfunction "1_1") (pintype "passive"))
      (node (ref "R21") (pin "2") (pinfunction "2_2") (pintype "passive"))
    )
    (net (code "65") (name "Net-(VR1-S)") (class "Default")
      (node (ref "R4") (pin "1") (pinfunction "1_1") (pintype "passive"))
      (node (ref "VR1") (pin "P$2") (pinfunction "S_P$2") (pintype "passive"))
    )
    (net (code "66") (name "Net-(VR2-S)") (class "Default")
      (node (ref "R8") (pin "1") (pinfunction "1_1") (pintype "passive"))
      (node (ref "VR2") (pin "P$2") (pinfunction "S_P$2") (pintype "passive"))
    )
    (net (code "67") (name "Net-(VR3-S)") (class "Default")
      (node (ref "R12") (pin "1") (pinfunction "1_1") (pintype "passive"))
      (node (ref "VR3") (pin "P$2") (pinfunction "S_P$2") (pintype "passive"))
    )
    (net (code "68") (name "Net-(VR4-S)") (class "Default")
      (node (ref "R16") (pin "1") (pinfunction "1_1") (pintype "passive"))
      (node (ref "VR4") (pin "P$2") (pinfunction "S_P$2") (pintype "passive"))
    )
    (net (code "69") (name "REF") (class "Default")
      (node (ref "J1") (pin "1") (pinfunction "1_1") (pintype "passive"))
    )
    (net (code "70") (name "SCL") (class "Default")
      (node (ref "P2") (pin "9") (pinfunction "9_9") (pintype "passive"))
    )
    (net (code "71") (name "SDA") (class "Default")
      (node (ref "P2") (pin "11") (pinfunction "11_11") (pintype "passive"))
    )
    (net (code "72") (name "VCC") (class "Default")
      (node (ref "C35") (pin "1") (pinfunction "1_1") (pintype "passive"))
      (node (ref "IC1") (pin "10") (pinfunction "+IN_10") (pintype "input"))
      (node (ref "IC1") (pin "12") (pinfunction "+IN_12") (pintype "input"))
      (node (ref "IC1") (pin "3") (pinfunction "+IN_3") (pintype "input"))
      (node (ref "IC1") (pin "5") (pinfunction "+IN_5") (pintype "input"))
      (node (ref "IC2") (pin "2") (pinfunction "C_2") (pintype "passive"))
      (node (ref "IC3") (pin "3") (pinfunction "+IN_3") (pintype "input"))
      (node (ref "IC3") (pin "5") (pinfunction "+IN_5") (pintype "input"))
      (node (ref "R58") (pin "2") (pinfunction "2_2") (pintype "passive"))
    )
    (net (code "73") (name "unconnected-(ALOL-1-PadP$3)") (class "Default")
      (node (ref "ALOL") (pin "P$3") (pinfunction "1_P$3") (pintype "passive"))
    )
    (net (code "74") (name "unconnected-(ALOL-2-PadP$1)") (class "Default")
      (node (ref "ALOL") (pin "P$1") (pinfunction "2_P$1") (pintype "passive"))
    )
    (net (code "75") (name "unconnected-(ALOL-3-PadP$2)") (class "Default")
      (node (ref "ALOL") (pin "P$2") (pinfunction "3_P$2") (pintype "passive"))
    )
    (net (code "76") (name "unconnected-(ALOR-1-PadP$3)") (class "Default")
      (node (ref "ALOR") (pin "P$3") (pinfunction "1_P$3") (pintype "passive"))
    )
    (net (code "77") (name "unconnected-(ALOR-2-PadP$1)") (class "Default")
      (node (ref "ALOR") (pin "P$1") (pinfunction "2_P$1") (pintype "passive"))
    )
    (net (code "78") (name "unconnected-(ALOR-3-PadP$2)") (class "Default")
      (node (ref "ALOR") (pin "P$2") (pinfunction "3_P$2") (pintype "passive"))
    )
    (net (code "79") (name "unconnected-(DAC1-3-PadP$2)") (class "Default")
      (node (ref "DAC1") (pin "P$2") (pinfunction "3_P$2") (pintype "passive"))
    )
    (net (code "80") (name "unconnected-(IC2-FB-Pad1)") (class "Default")
      (node (ref "IC2") (pin "1") (pinfunction "FB_1") (pintype "passive"))
    )
    (net (code "81") (name "unconnected-(P1-Pad1)") (class "Default")
      (node (ref "P1") (pin "1") (pinfunction "1_1") (pintype "passive"))
    )
    (net (code "82") (name "unconnected-(P1-Pad2)") (class "Default")
      (node (ref "P1") (pin "2") (pinfunction "2_2") (pintype "passive"))
    )
    (net (code "83") (name "unconnected-(P1-Pad3)") (class "Default")
      (node (ref "P1") (pin "3") (pinfunction "3_3") (pintype "passive"))
    )
    (net (code "84") (name "unconnected-(P1-Pad4)") (class "Default")
      (node (ref "P1") (pin "4") (pinfunction "4_4") (pintype "passive"))
    )
    (net (code "85") (name "unconnected-(P1-Pad5)") (class "Default")
      (node (ref "P1") (pin "5") (pinfunction "5_5") (pintype "passive"))
    )
    (net (code "86") (name "unconnected-(P1-Pad6)") (class "Default")
      (node (ref "P1") (pin "6") (pinfunction "6_6") (pintype "passive"))
    )
    (net (code "87") (name "unconnected-(P1-Pad7)") (class "Default")
      (node (ref "P1") (pin "7") (pinfunction "7_7") (pintype "passive"))
    )
    (net (code "88") (name "unconnected-(P1-Pad8)") (class "Default")
      (node (ref "P1") (pin "8") (pinfunction "8_8") (pintype "passive"))
    )
    (net (code "89") (name "unconnected-(P1-Pad9)") (class "Default")
      (node (ref "P1") (pin "9") (pinfunction "9_9") (pintype "passive"))
    )
    (net (code "90") (name "unconnected-(P1-Pad10)") (class "Default")
      (node (ref "P1") (pin "10") (pinfunction "10_10") (pintype "passive"))
    )
    (net (code "91") (name "unconnected-(P1-Pad11)") (class "Default")
      (node (ref "P1") (pin "11") (pinfunction "11_11") (pintype "passive"))
    )
    (net (code "92") (name "unconnected-(P1-Pad12)") (class "Default")
      (node (ref "P1") (pin "12") (pinfunction "12_12") (pintype "passive"))
    )
    (net (code "93") (name "unconnected-(P1-Pad13)") (class "Default")
      (node (ref "P1") (pin "13") (pinfunction "13_13") (pintype "passive"))
    )
    (net (code "94") (name "unconnected-(P1-Pad15)") (class "Default")
      (node (ref "P1") (pin "15") (pinfunction "15_15") (pintype "passive"))
    )
    (net (code "95") (name "unconnected-(P1-Pad17)") (class "Default")
      (node (ref "P1") (pin "17") (pinfunction "17_17") (pintype "passive"))
    )
    (net (code "96") (name "unconnected-(P1-Pad18)") (class "Default")
      (node (ref "P1") (pin "18") (pinfunction "18_18") (pintype "passive"))
    )
    (net (code "97") (name "unconnected-(P1-Pad19)") (class "Default")
      (node (ref "P1") (pin "19") (pinfunction "19_19") (pintype "passive"))
    )
    (net (code "98") (name "unconnected-(P1-Pad20)") (class "Default")
      (node (ref "P1") (pin "20") (pinfunction "20_20") (pintype "passive"))
    )
    (net (code "99") (name "unconnected-(P1-Pad21)") (class "Default")
      (node (ref "P1") (pin "21") (pinfunction "21_21") (pintype "passive"))
    )
    (net (code "100") (name "unconnected-(P1-Pad23)") (class "Default")
      (node (ref "P1") (pin "23") (pinfunction "23_23") (pintype "passive"))
    )
    (net (code "101") (name "unconnected-(P1-Pad25)") (class "Default")
      (node (ref "P1") (pin "25") (pinfunction "25_25") (pintype "passive"))
    )
    (net (code "102") (name "unconnected-(P1-Pad26)") (class "Default")
      (node (ref "P1") (pin "26") (pinfunction "26_26") (pintype "passive"))
    )
    (net (code "103") (name "unconnected-(P1-Pad27)") (class "Default")
      (node (ref "P1") (pin "27") (pinfunction "27_27") (pintype "passive"))
    )
    (net (code "104") (name "unconnected-(P1-Pad28)") (class "Default")
      (node (ref "P1") (pin "28") (pinfunction "28_28") (pintype "passive"))
    )
    (net (code "105") (name "unconnected-(P1-Pad29)") (class "Default")
      (node (ref "P1") (pin "29") (pinfunction "29_29") (pintype "passive"))
    )
    (net (code "106") (name "unconnected-(P1-Pad31)") (class "Default")
      (node (ref "P1") (pin "31") (pinfunction "31_31") (pintype "passive"))
    )
    (net (code "107") (name "unconnected-(P1-Pad33)") (class "Default")
      (node (ref "P1") (pin "33") (pinfunction "33_33") (pintype "passive"))
    )
    (net (code "108") (name "unconnected-(P1-Pad34)") (class "Default")
      (node (ref "P1") (pin "34") (pinfunction "34_34") (pintype "passive"))
    )
    (net (code "109") (name "unconnected-(P1-Pad36)") (class "Default")
      (node (ref "P1") (pin "36") (pinfunction "36_36") (pintype "passive"))
    )
    (net (code "110") (name "unconnected-(P2-Pad3)") (class "Default")
      (node (ref "P2") (pin "3") (pinfunction "3_3") (pintype "passive"))
    )
    (net (code "111") (name "unconnected-(P2-Pad5)") (class "Default")
      (node (ref "P2") (pin "5") (pinfunction "5_5") (pintype "passive"))
    )
    (net (code "112") (name "unconnected-(P2-Pad7)") (class "Default")
      (node (ref "P2") (pin "7") (pinfunction "7_7") (pintype "passive"))
    )
    (net (code "113") (name "unconnected-(P2-Pad12)") (class "Default")
      (node (ref "P2") (pin "12") (pinfunction "12_12") (pintype "passive"))
    )
    (net (code "114") (name "unconnected-(P2-Pad13)") (class "Default")
      (node (ref "P2") (pin "13") (pinfunction "13_13") (pintype "passive"))
    )
    (net (code "115") (name "unconnected-(P2-Pad14)") (class "Default")
      (node (ref "P2") (pin "14") (pinfunction "14_14") (pintype "passive"))
    )
    (net (code "116") (name "unconnected-(P2-Pad15)") (class "Default")
      (node (ref "P2") (pin "15") (pinfunction "15_15") (pintype "passive"))
    )
    (net (code "117") (name "unconnected-(P2-Pad16)") (class "Default")
      (node (ref "P2") (pin "16") (pinfunction "16_16") (pintype "passive"))
    )
    (net (code "118") (name "unconnected-(P2-Pad17)") (class "Default")
      (node (ref "P2") (pin "17") (pinfunction "17_17") (pintype "passive"))
    )
    (net (code "119") (name "unconnected-(P2-Pad19)") (class "Default")
      (node (ref "P2") (pin "19") (pinfunction "19_19") (pintype "passive"))
    )
    (net (code "120") (name "unconnected-(P2-Pad26)") (class "Default")
      (node (ref "P2") (pin "26") (pinfunction "26_26") (pintype "passive"))
    )
    (net (code "121") (name "unconnected-(P2-Pad28)") (class "Default")
      (node (ref "P2") (pin "28") (pinfunction "28_28") (pintype "passive"))
    )
    (net (code "122") (name "unconnected-(P2-Pad29)") (class "Default")
      (node (ref "P2") (pin "29") (pinfunction "29_29") (pintype "passive"))
    )
    (net (code "123") (name "unconnected-(P2-Pad30)") (class "Default")
      (node (ref "P2") (pin "30") (pinfunction "30_30") (pintype "passive"))
    )
    (net (code "124") (name "unconnected-(P2-Pad31)") (class "Default")
      (node (ref "P2") (pin "31") (pinfunction "31_31") (pintype "passive"))
    )
    (net (code "125") (name "unconnected-(P2-Pad32)") (class "Default")
      (node (ref "P2") (pin "32") (pinfunction "32_32") (pintype "passive"))
    )
    (net (code "126") (name "unconnected-(P2-Pad33)") (class "Default")
      (node (ref "P2") (pin "33") (pinfunction "33_33") (pintype "passive"))
    )
    (net (code "127") (name "unconnected-(P2-Pad34)") (class "Default")
      (node (ref "P2") (pin "34") (pinfunction "34_34") (pintype "passive"))
    )
    (net (code "128") (name "unconnected-(P2-Pad36)") (class "Default")
      (node (ref "P2") (pin "36") (pinfunction "36_36") (pintype "passive"))
    )
  )
)
